# thread.net
KiCad netlist of a schematic drawn in Altium Designer
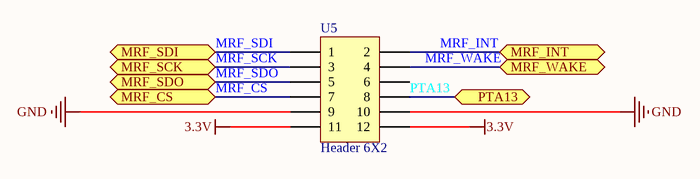
[diagram p0: thread.SchDoc]

(export (version "E")
  (design (tool "Eeschema 10.0.6"))
  (components
    (comp (ref "U5")
      (value "Header 6X2")
      (footprint "HDR2X6")
      (description "Header, 6-Pin, Dual row")
      (fields (field (name "PUBLISHER") "Altium Limited"))
      (libsource (lib "Sparks") (part "Header 6X2"))
    )
  )
  (nets
    (net (code "1") (name "/MRF_CS") (class "Default")
      (node (ref "U5") (pin "7") (pinfunction "7_7") (pintype "passive"))
    )
    (net (code "2") (name "/MRF_INT") (class "Default")
      (node (ref "U5") (pin "2") (pinfunction "2_2") (pintype "passive"))
    )
    (net (code "3") (name "/MRF_SCK") (class "Default")
      (node (ref "U5") (pin "3") (pinfunction "3_3") (pintype "passive"))
    )
    (net (code "4") (name "/MRF_SDI") (class "Default")
      (node (ref "U5") (pin "1") (pinfunction "1_1") (pintype "passive"))
    )
    (net (code "5") (name "/MRF_SDO") (class "Default")
      (node (ref "U5") (pin "5") (pinfunction "5_5") (pintype "passive"))
    )
    (net (code "6") (name "/MRF_WAKE") (class "Default")
      (node (ref "U5") (pin "4") (pinfunction "4_4") (pintype "passive"))
    )
    (net (code "7") (name "/PTA13") (class "Default")
      (node (ref "U5") (pin "8") (pinfunction "8_8") (pintype "passive"))
    )
    (net (code "8") (name "3.3V") (class "Default")
      (node (ref "U5") (pin "11") (pinfunction "11_11") (pintype "passive"))
      (node (ref "U5") (pin "12") (pinfunction "12_12") (pintype "passive"))
    )
    (net (code "9") (name "GND") (class "Default")
      (node (ref "U5") (pin "10") (pinfunction "10_10") (pintype "passive"))
      (node (ref "U5") (pin "9") (pinfunction "9_9") (pintype "passive"))
    )
    (net (code "10") (name "unconnected-(U5-Pad6)") (class "Default")
      (node (ref "U5") (pin "6") (pinfunction "6_6") (pintype "passive"))
    )
  )
)
